# Mezz_Board.net
KiCad netlist of a schematic drawn in Altium Designer
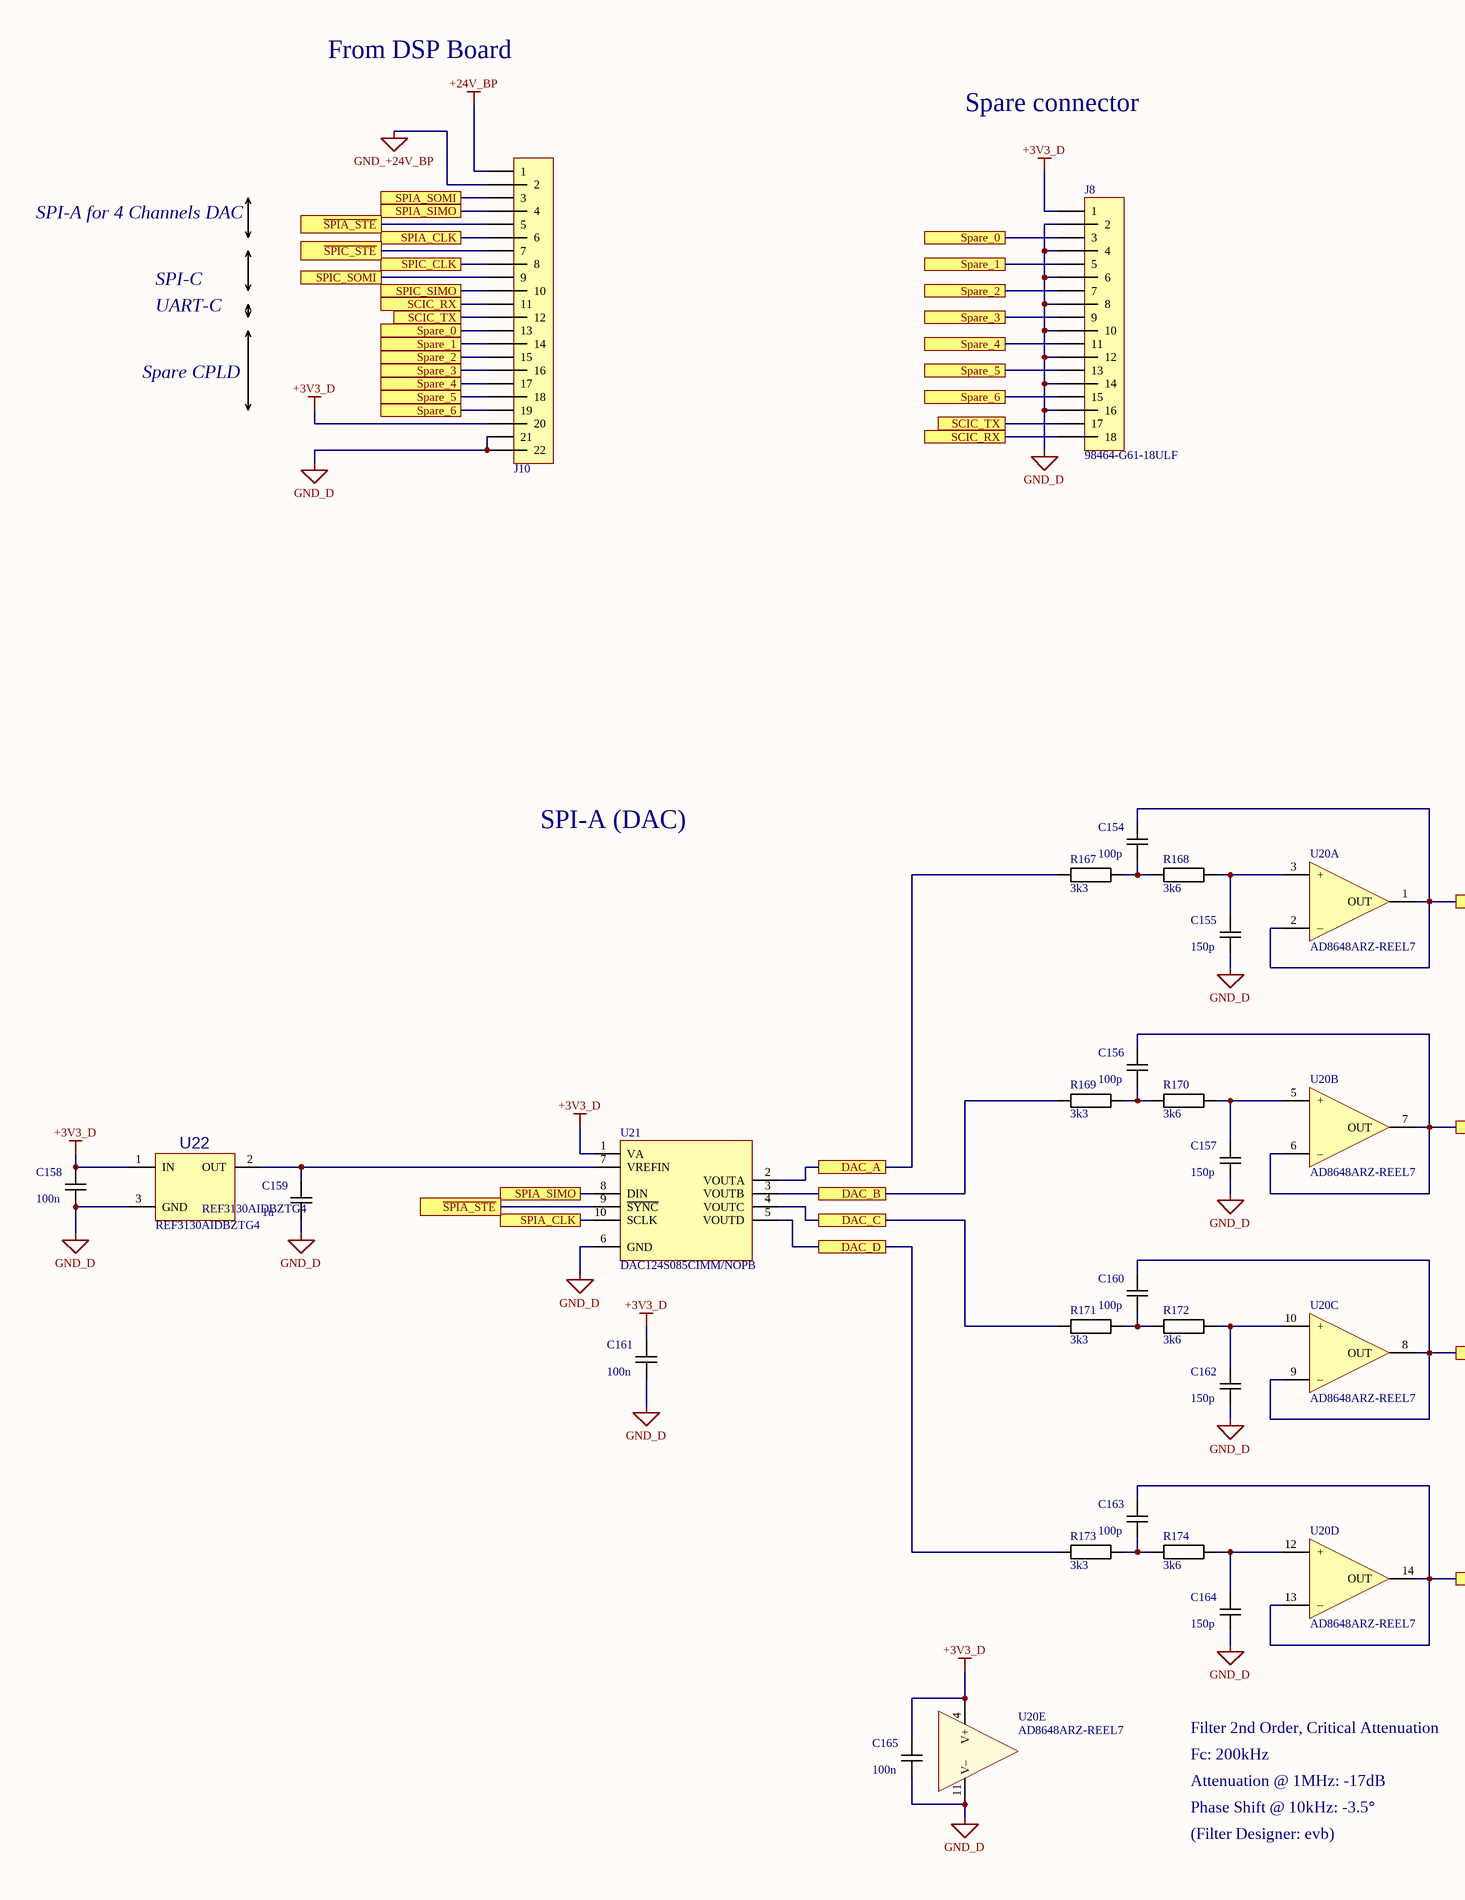
[diagram p0: Mezz_Board.SchDoc, left]
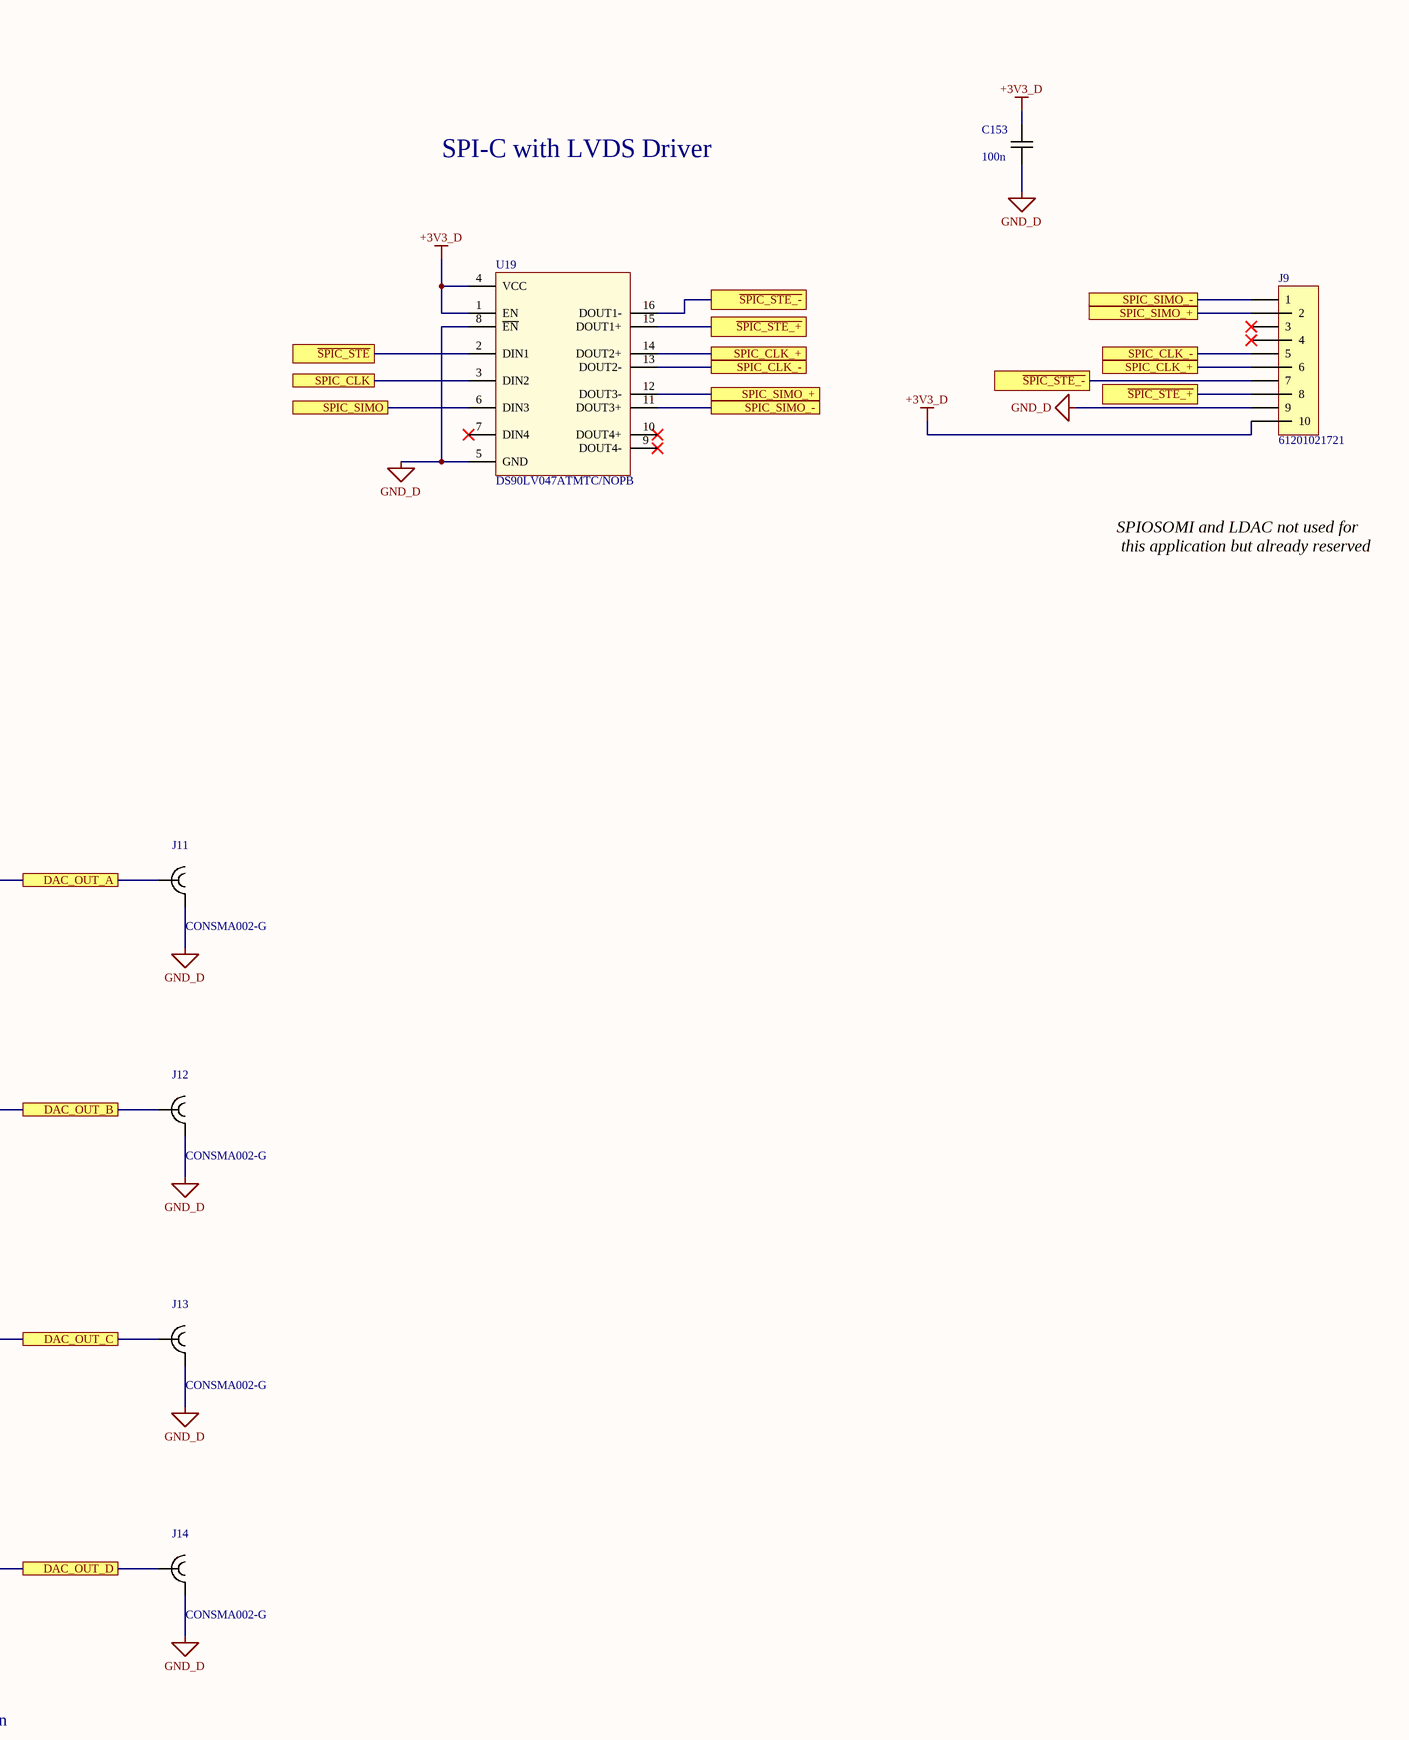
[diagram p1: Mezz_Board.SchDoc, right]

(export (version "E")
  (design (tool "Eeschema 10.0.6"))
  (components
    (comp (ref "C153")
      (value "100n")
      (footprint "CAPACITOR 2012 REFLOW")
      (description "Capacitor X7R 10% 50V 2012(0805)")
      (libsource (lib "Capacitor") (part "Capacitor"))
    )
    (comp (ref "C154")
      (value "100p")
      (footprint "CAPACITOR 2012 REFLOW")
      (description "Capacitor X7R 10% 50V 2012(0805)")
      (libsource (lib "Capacitor") (part "Capacitor"))
    )
    (comp (ref "C155")
      (value "150p")
      (footprint "CAPACITOR 2012 REFLOW")
      (description "Capacitor X7R 10% 50V 2012(0805)")
      (libsource (lib "Capacitor") (part "Capacitor"))
    )
    (comp (ref "C156")
      (value "100p")
      (footprint "CAPACITOR 2012 REFLOW")
      (description "Capacitor X7R 10% 50V 2012(0805)")
      (libsource (lib "Capacitor") (part "Capacitor"))
    )
    (comp (ref "C157")
      (value "150p")
      (footprint "CAPACITOR 2012 REFLOW")
      (description "Capacitor X7R 10% 50V 2012(0805)")
      (libsource (lib "Capacitor") (part "Capacitor"))
    )
    (comp (ref "C158")
      (value "100n")
      (footprint "CAPACITOR 2012 REFLOW")
      (description "Capacitor X7R 10% 50V 2012(0805)")
      (libsource (lib "Capacitor") (part "Capacitor"))
    )
    (comp (ref "C159")
      (value "1u")
      (footprint "CAPACITOR 2012 REFLOW")
      (description "Capacitor X7R 10% 10V 2012(0805)")
      (libsource (lib "Capacitor") (part "Capacitor"))
    )
    (comp (ref "C160")
      (value "100p")
      (footprint "CAPACITOR 2012 REFLOW")
      (description "Capacitor X7R 10% 50V 2012(0805)")
      (libsource (lib "Capacitor") (part "Capacitor"))
    )
    (comp (ref "C161")
      (value "100n")
      (footprint "CAPACITOR 1608 REFLOW")
      (description "Capacitor X7R 10% 50V 1608(0603)")
      (libsource (lib "Capacitor") (part "Capacitor"))
    )
    (comp (ref "C162")
      (value "150p")
      (footprint "CAPACITOR 2012 REFLOW")
      (description "Capacitor X7R 10% 50V 2012(0805)")
      (libsource (lib "Capacitor") (part "Capacitor"))
    )
    (comp (ref "C163")
      (value "100p")
      (footprint "CAPACITOR 2012 REFLOW")
      (description "Capacitor X7R 10% 50V 2012(0805)")
      (libsource (lib "Capacitor") (part "Capacitor"))
    )
    (comp (ref "C164")
      (value "150p")
      (footprint "CAPACITOR 2012 REFLOW")
      (description "Capacitor X7R 10% 50V 2012(0805)")
      (libsource (lib "Capacitor") (part "Capacitor"))
    )
    (comp (ref "C165")
      (value "100n")
      (footprint "CAPACITOR 1608 REFLOW")
      (description "Capacitor X7R 10% 50V 1608(0603)")
      (libsource (lib "Capacitor") (part "Capacitor"))
    )
    (comp (ref "J8")
      (value "98464-G61-18ULF")
      (footprint "FlatCable2x9 2MM Right Angle TH FCI 98614-G61-18ULF")
      (description "FlatCable2x9")
      (fields (field (name "MANUFACTURER") "Amphenol FCI"))
      (libsource (lib "Connector") (part "FlatCable2x9"))
    )
    (comp (ref "J9")
      (value "61201021721")
      (footprint "FlatCable2x5 2.54MM RIGHT ANGLE TH")
      (description "FlatCable2x5")
      (fields (field (name "MANUFACTURER") "Wurth Elektronik"))
      (libsource (lib "Connector") (part "FlatCable2x5"))
    )
    (comp (ref "J10")
      (value "*")
      (footprint "PinHeader2x11 P2.54 A")
      (description "Plug connector")
      (libsource (lib "PinHeader") (part "PinHeader2x11"))
    )
    (comp (ref "J11")
      (value "CONSMA002-G")
      (footprint "SMA TH Right Angle Linx CONSMA002")
      (description "SMA TH RIGHT ANGLE LINX CONSMA002")
      (fields (field (name "MANUFACTURER") "Linx Technologies"))
      (libsource (lib "Connector") (part "SMA TH RIGHT ANGLE LINX CONSMA002"))
    )
    (comp (ref "J12")
      (value "CONSMA002-G")
      (footprint "SMA TH Right Angle Linx CONSMA002")
      (description "SMA TH RIGHT ANGLE LINX CONSMA002")
      (fields (field (name "MANUFACTURER") "Linx Technologies"))
      (libsource (lib "Connector") (part "SMA TH RIGHT ANGLE LINX CONSMA002"))
    )
    (comp (ref "J13")
      (value "CONSMA002-G")
      (footprint "SMA TH Right Angle Linx CONSMA002")
      (description "SMA TH RIGHT ANGLE LINX CONSMA002")
      (fields (field (name "MANUFACTURER") "Linx Technologies"))
      (libsource (lib "Connector") (part "SMA TH RIGHT ANGLE LINX CONSMA002"))
    )
    (comp (ref "J14")
      (value "CONSMA002-G")
      (footprint "SMA TH Right Angle Linx CONSMA002")
      (description "SMA TH RIGHT ANGLE LINX CONSMA002")
      (fields (field (name "MANUFACTURER") "Linx Technologies"))
      (libsource (lib "Connector") (part "SMA TH RIGHT ANGLE LINX CONSMA002"))
    )
    (comp (ref "R167")
      (value "3k3")
      (footprint "RESISTOR 2012 REFLOW")
      (description "Resistor 1% 50V 125mW 2012(0805)")
      (libsource (lib "Resistor") (part "Resistor"))
    )
    (comp (ref "R168")
      (value "3k6")
      (footprint "RESISTOR 2012 REFLOW")
      (description "Resistor 1% 50V 125mW 2012(0805)")
      (libsource (lib "Resistor") (part "Resistor"))
    )
    (comp (ref "R169")
      (value "3k3")
      (footprint "RESISTOR 2012 REFLOW")
      (description "Resistor 1% 50V 125mW 2012(0805)")
      (libsource (lib "Resistor") (part "Resistor"))
    )
    (comp (ref "R170")
      (value "3k6")
      (footprint "RESISTOR 2012 REFLOW")
      (description "Resistor 1% 50V 125mW 2012(0805)")
      (libsource (lib "Resistor") (part "Resistor"))
    )
    (comp (ref "R171")
      (value "3k3")
      (footprint "RESISTOR 2012 REFLOW")
      (description "Resistor 1% 50V 125mW 2012(0805)")
      (libsource (lib "Resistor") (part "Resistor"))
    )
    (comp (ref "R172")
      (value "3k6")
      (footprint "RESISTOR 2012 REFLOW")
      (description "Resistor 1% 50V 125mW 2012(0805)")
      (libsource (lib "Resistor") (part "Resistor"))
    )
    (comp (ref "R173")
      (value "3k3")
      (footprint "RESISTOR 2012 REFLOW")
      (description "Resistor 1% 50V 125mW 2012(0805)")
      (libsource (lib "Resistor") (part "Resistor"))
    )
    (comp (ref "R174")
      (value "3k6")
      (footprint "RESISTOR 2012 REFLOW")
      (description "Resistor 1% 50V 125mW 2012(0805)")
      (libsource (lib "Resistor") (part "Resistor"))
    )
    (comp (ref "U19")
      (value "DS90LV047ATMTC/NOPB")
      (footprint "TSSOP16 P0.65 C5.0x4.5 H1.1")
      (description "DS90LV047A 3-V LVDS Quad CMOS Differential Line Driver")
      (fields (field (name "MANUFACTURER") "Texas Instruments"))
      (libsource (lib "IntegratedCircuit") (part "DS90LV047A"))
    )
    (comp (ref "U20")
      (value "AD8648ARZ-REEL7")
      (footprint "SO14 P1.27 C4.0X8.8 H1.75")
      (description "Generic quad OPA 14 pins")
      (fields (field (name "MANUFACTURER") "Analog Devices"))
      (libsource (lib "Amplifier") (part "OPA QUAD"))
    )
    (comp (ref "U21")
      (value "DAC124S085CIMM/NOPB")
      (footprint "VSSOP10 P0.5 C3.1X3.1 H1.1")
      (description "DAC124S085 12-Bit Micro Power Quad Digital-to-Analog Converter With Rail-to-Rail Output")
      (fields (field (name "MANUFACTURER") "Texas Instruments"))
      (libsource (lib "Converter") (part "DAC124S085CIMM"))
    )
    (comp (ref "U22")
      (value "REF3130AIDBZTG4")
      (footprint "SOT23 P0.95 C1.6x3.0 H1.3")
      (description "Generic Positive Voltage Reference")
      (fields
        (field (name "ALTIUM_VALUE") "REF3130AIDBZTG4")
        (field (name "MANUFACTURER") "Texas Instruments")
      )
      (libsource (lib "Regulator") (part "REFERENCE SOT23 IN-OUT- GND"))
    )
  )
  (nets
    (net (code "1") (name "+3V3_D") (class "Default")
      (node (ref "C153") (pin "2") (pinfunction "2_2") (pintype "passive"))
      (node (ref "C158") (pin "2") (pinfunction "2_2") (pintype "passive"))
      (node (ref "C161") (pin "2") (pinfunction "2_2") (pintype "passive"))
      (node (ref "C165") (pin "2") (pinfunction "2_2") (pintype "passive"))
      (node (ref "J10") (pin "20") (pinfunction "20_20") (pintype "passive"))
      (node (ref "J8") (pin "1") (pinfunction "1_1") (pintype "passive"))
      (node (ref "J9") (pin "10") (pinfunction "10_10") (pintype "passive"))
      (node (ref "U19") (pin "1") (pinfunction "EN_1") (pintype "passive"))
      (node (ref "U19") (pin "4") (pinfunction "VCC_4") (pintype "passive"))
      (node (ref "U20") (pin "4") (pinfunction "V+_4") (pintype "passive"))
      (node (ref "U21") (pin "1") (pinfunction "VA_1") (pintype "passive"))
      (node (ref "U22") (pin "1") (pinfunction "IN_1") (pintype "passive"))
    )
    (net (code "2") (name "+24V_BP") (class "Default")
      (node (ref "J10") (pin "1") (pinfunction "1_1") (pintype "passive"))
    )
    (net (code "3") (name "/DAC_A") (class "Default")
      (node (ref "R167") (pin "1") (pinfunction "1_1") (pintype "passive"))
      (node (ref "U21") (pin "2") (pinfunction "VOUTA_2") (pintype "passive"))
    )
    (net (code "4") (name "/DAC_B") (class "Default")
      (node (ref "R169") (pin "1") (pinfunction "1_1") (pintype "passive"))
      (node (ref "U21") (pin "3") (pinfunction "VOUTB_3") (pintype "passive"))
    )
    (net (code "5") (name "/DAC_C") (class "Default")
      (node (ref "R171") (pin "1") (pinfunction "1_1") (pintype "passive"))
      (node (ref "U21") (pin "4") (pinfunction "VOUTC_4") (pintype "passive"))
    )
    (net (code "6") (name "/DAC_D") (class "Default")
      (node (ref "R173") (pin "1") (pinfunction "1_1") (pintype "passive"))
      (node (ref "U21") (pin "5") (pinfunction "VOUTD_5") (pintype "passive"))
    )
    (net (code "7") (name "/DAC_OUT_A") (class "Default")
      (node (ref "C154") (pin "2") (pinfunction "2_2") (pintype "passive"))
      (node (ref "J11") (pin "1") (pinfunction "1_1") (pintype "passive"))
      (node (ref "U20") (pin "1") (pinfunction "OUT_1") (pintype "passive"))
      (node (ref "U20") (pin "2") (pinfunction "–_2") (pintype "passive"))
    )
    (net (code "8") (name "/DAC_OUT_B") (class "Default")
      (node (ref "C156") (pin "2") (pinfunction "2_2") (pintype "passive"))
      (node (ref "J12") (pin "1") (pinfunction "1_1") (pintype "passive"))
      (node (ref "U20") (pin "6") (pinfunction "–_6") (pintype "passive"))
      (node (ref "U20") (pin "7") (pinfunction "OUT_7") (pintype "passive"))
    )
    (net (code "9") (name "/DAC_OUT_C") (class "Default")
      (node (ref "C160") (pin "2") (pinfunction "2_2") (pintype "passive"))
      (node (ref "J13") (pin "1") (pinfunction "1_1") (pintype "passive"))
      (node (ref "U20") (pin "8") (pinfunction "OUT_8") (pintype "passive"))
      (node (ref "U20") (pin "9") (pinfunction "–_9") (pintype "passive"))
    )
    (net (code "10") (name "/DAC_OUT_D") (class "Default")
      (node (ref "C163") (pin "2") (pinfunction "2_2") (pintype "passive"))
      (node (ref "J14") (pin "1") (pinfunction "1_1") (pintype "passive"))
      (node (ref "U20") (pin "13") (pinfunction "–_13") (pintype "passive"))
      (node (ref "U20") (pin "14") (pinfunction "OUT_14") (pintype "passive"))
    )
    (net (code "11") (name "/SCIC_RX") (class "Default")
      (node (ref "J10") (pin "11") (pinfunction "11_11") (pintype "passive"))
      (node (ref "J8") (pin "18") (pinfunction "18_18") (pintype "passive"))
    )
    (net (code "12") (name "/SCIC_TX") (class "Default")
      (node (ref "J10") (pin "12") (pinfunction "12_12") (pintype "passive"))
      (node (ref "J8") (pin "17") (pinfunction "17_17") (pintype "passive"))
    )
    (net (code "13") (name "/SPIA_CLK") (class "Default")
      (node (ref "J10") (pin "6") (pinfunction "6_6") (pintype "passive"))
      (node (ref "U21") (pin "10") (pinfunction "SCLK_10") (pintype "passive"))
    )
    (net (code "14") (name "/SPIA_SIMO") (class "Default")
      (node (ref "J10") (pin "4") (pinfunction "4_4") (pintype "passive"))
      (node (ref "U21") (pin "8") (pinfunction "DIN_8") (pintype "passive"))
    )
    (net (code "15") (name "/SPIA_SOMI") (class "Default")
      (node (ref "J10") (pin "3") (pinfunction "3_3") (pintype "passive"))
    )
    (net (code "16") (name "/SPIC_CLK") (class "Default")
      (node (ref "J10") (pin "8") (pinfunction "8_8") (pintype "passive"))
      (node (ref "U19") (pin "3") (pinfunction "DIN2_3") (pintype "passive"))
    )
    (net (code "17") (name "/SPIC_CLK_+") (class "Default")
      (node (ref "J9") (pin "6") (pinfunction "6_6") (pintype "passive"))
      (node (ref "U19") (pin "14") (pinfunction "DOUT2+_14") (pintype "passive"))
    )
    (net (code "18") (name "/SPIC_CLK_-") (class "Default")
      (node (ref "J9") (pin "5") (pinfunction "5_5") (pintype "passive"))
      (node (ref "U19") (pin "13") (pinfunction "DOUT2-_13") (pintype "passive"))
    )
    (net (code "19") (name "/SPIC_SIMO") (class "Default")
      (node (ref "J10") (pin "10") (pinfunction "10_10") (pintype "passive"))
      (node (ref "U19") (pin "6") (pinfunction "DIN3_6") (pintype "passive"))
    )
    (net (code "20") (name "/SPIC_SIMO_+") (class "Default")
      (node (ref "J9") (pin "2") (pinfunction "2_2") (pintype "passive"))
      (node (ref "U19") (pin "12") (pinfunction "DOUT3-_12") (pintype "passive"))
    )
    (net (code "21") (name "/SPIC_SIMO_-") (class "Default")
      (node (ref "J9") (pin "1") (pinfunction "1_1") (pintype "passive"))
      (node (ref "U19") (pin "11") (pinfunction "DOUT3+_11") (pintype "passive"))
    )
    (net (code "22") (name "/SPIC_SOMI") (class "Default")
      (node (ref "J10") (pin "9") (pinfunction "9_9") (pintype "passive"))
    )
    (net (code "23") (name "/Spare_0") (class "Default")
      (node (ref "J10") (pin "13") (pinfunction "13_13") (pintype "passive"))
      (node (ref "J8") (pin "3") (pinfunction "3_3") (pintype "passive"))
    )
    (net (code "24") (name "/Spare_1") (class "Default")
      (node (ref "J10") (pin "14") (pinfunction "14_14") (pintype "passive"))
      (node (ref "J8") (pin "5") (pinfunction "5_5") (pintype "passive"))
    )
    (net (code "25") (name "/Spare_2") (class "Default")
      (node (ref "J10") (pin "15") (pinfunction "15_15") (pintype "passive"))
      (node (ref "J8") (pin "7") (pinfunction "7_7") (pintype "passive"))
    )
    (net (code "26") (name "/Spare_3") (class "Default")
      (node (ref "J10") (pin "16") (pinfunction "16_16") (pintype "passive"))
      (node (ref "J8") (pin "9") (pinfunction "9_9") (pintype "passive"))
    )
    (net (code "27") (name "/Spare_4") (class "Default")
      (node (ref "J10") (pin "17") (pinfunction "17_17") (pintype "passive"))
      (node (ref "J8") (pin "11") (pinfunction "11_11") (pintype "passive"))
    )
    (net (code "28") (name "/Spare_5") (class "Default")
      (node (ref "J10") (pin "18") (pinfunction "18_18") (pintype "passive"))
      (node (ref "J8") (pin "13") (pinfunction "13_13") (pintype "passive"))
    )
    (net (code "29") (name "/Spare_6") (class "Default")
      (node (ref "J10") (pin "19") (pinfunction "19_19") (pintype "passive"))
      (node (ref "J8") (pin "15") (pinfunction "15_15") (pintype "passive"))
    )
    (net (code "30") (name "/~{SPIA_STE}") (class "Default")
      (node (ref "J10") (pin "5") (pinfunction "5_5") (pintype "passive"))
      (node (ref "U21") (pin "9") (pinfunction "~{SYNC}_9") (pintype "passive"))
    )
    (net (code "31") (name "/~{SPIC_STE_+}") (class "Default")
      (node (ref "J9") (pin "8") (pinfunction "8_8") (pintype "passive"))
      (node (ref "U19") (pin "15") (pinfunction "DOUT1+_15") (pintype "passive"))
    )
    (net (code "32") (name "/~{SPIC_STE_-}") (class "Default")
      (node (ref "J9") (pin "7") (pinfunction "7_7") (pintype "passive"))
      (node (ref "U19") (pin "16") (pinfunction "DOUT1-_16") (pintype "passive"))
    )
    (net (code "33") (name "/~{SPIC_STE}") (class "Default")
      (node (ref "J10") (pin "7") (pinfunction "7_7") (pintype "passive"))
      (node (ref "U19") (pin "2") (pinfunction "DIN1_2") (pintype "passive"))
    )
    (net (code "34") (name "GND_+24V_BP") (class "Default")
      (node (ref "J10") (pin "2") (pinfunction "2_2") (pintype "passive"))
    )
    (net (code "35") (name "GND_D") (class "Default")
      (node (ref "C153") (pin "1") (pinfunction "1_1") (pintype "passive"))
      (node (ref "C155") (pin "1") (pinfunction "1_1") (pintype "passive"))
      (node (ref "C157") (pin "1") (pinfunction "1_1") (pintype "passive"))
      (node (ref "C158") (pin "1") (pinfunction "1_1") (pintype "passive"))
      (node (ref "C159") (pin "1") (pinfunction "1_1") (pintype "passive"))
      (node (ref "C161") (pin "1") (pinfunction "1_1") (pintype "passive"))
      (node (ref "C162") (pin "1") (pinfunction "1_1") (pintype "passive"))
      (node (ref "C164") (pin "1") (pinfunction "1_1") (pintype "passive"))
      (node (ref "C165") (pin "1") (pinfunction "1_1") (pintype "passive"))
      (node (ref "J10") (pin "21") (pinfunction "21_21") (pintype "passive"))
      (node (ref "J10") (pin "22") (pinfunction "22_22") (pintype "passive"))
      (node (ref "J11") (pin "2") (pinfunction "2_2") (pintype "passive"))
      (node (ref "J12") (pin "2") (pinfunction "2_2") (pintype "passive"))
      (node (ref "J13") (pin "2") (pinfunction "2_2") (pintype "passive"))
      (node (ref "J14") (pin "2") (pinfunction "2_2") (pintype "passive"))
      (node (ref "J8") (pin "10") (pinfunction "10_10") (pintype "passive"))
      (node (ref "J8") (pin "12") (pinfunction "12_12") (pintype "passive"))
      (node (ref "J8") (pin "14") (pinfunction "14_14") (pintype "passive"))
      (node (ref "J8") (pin "16") (pinfunction "16_16") (pintype "passive"))
      (node (ref "J8") (pin "2") (pinfunction "2_2") (pintype "passive"))
      (node (ref "J8") (pin "4") (pinfunction "4_4") (pintype "passive"))
      (node (ref "J8") (pin "6") (pinfunction "6_6") (pintype "passive"))
      (node (ref "J8") (pin "8") (pinfunction "8_8") (pintype "passive"))
      (node (ref "J9") (pin "9") (pinfunction "9_9") (pintype "passive"))
      (node (ref "U19") (pin "5") (pinfunction "GND_5") (pintype "passive"))
      (node (ref "U19") (pin "8") (pinfunction "~{EN}_8") (pintype "passive"))
      (node (ref "U20") (pin "11") (pinfunction "V–_11") (pintype "passive"))
      (node (ref "U21") (pin "6") (pinfunction "GND_6") (pintype "passive"))
      (node (ref "U22") (pin "3") (pinfunction "GND_3") (pintype "passive"))
    )
    (net (code "36") (name "Net-(C154-Pad1)") (class "Default")
      (node (ref "C154") (pin "1") (pinfunction "1_1") (pintype "passive"))
      (node (ref "R167") (pin "2") (pinfunction "2_2") (pintype "passive"))
      (node (ref "R168") (pin "1") (pinfunction "1_1") (pintype "passive"))
    )
    (net (code "37") (name "Net-(C156-Pad1)") (class "Default")
      (node (ref "C156") (pin "1") (pinfunction "1_1") (pintype "passive"))
      (node (ref "R169") (pin "2") (pinfunction "2_2") (pintype "passive"))
      (node (ref "R170") (pin "1") (pinfunction "1_1") (pintype "passive"))
    )
    (net (code "38") (name "Net-(C160-Pad1)") (class "Default")
      (node (ref "C160") (pin "1") (pinfunction "1_1") (pintype "passive"))
      (node (ref "R171") (pin "2") (pinfunction "2_2") (pintype "passive"))
      (node (ref "R172") (pin "1") (pinfunction "1_1") (pintype "passive"))
    )
    (net (code "39") (name "Net-(C163-Pad1)") (class "Default")
      (node (ref "C163") (pin "1") (pinfunction "1_1") (pintype "passive"))
      (node (ref "R173") (pin "2") (pinfunction "2_2") (pintype "passive"))
      (node (ref "R174") (pin "1") (pinfunction "1_1") (pintype "passive"))
    )
    (net (code "40") (name "Net-(U20A-+)") (class "Default")
      (node (ref "C155") (pin "2") (pinfunction "2_2") (pintype "passive"))
      (node (ref "R168") (pin "2") (pinfunction "2_2") (pintype "passive"))
      (node (ref "U20") (pin "3") (pinfunction "+_3") (pintype "passive"))
    )
    (net (code "41") (name "Net-(U20B-+)") (class "Default")
      (node (ref "C157") (pin "2") (pinfunction "2_2") (pintype "passive"))
      (node (ref "R170") (pin "2") (pinfunction "2_2") (pintype "passive"))
      (node (ref "U20") (pin "5") (pinfunction "+_5") (pintype "passive"))
    )
    (net (code "42") (name "Net-(U20C-+)") (class "Default")
      (node (ref "C162") (pin "2") (pinfunction "2_2") (pintype "passive"))
      (node (ref "R172") (pin "2") (pinfunction "2_2") (pintype "passive"))
      (node (ref "U20") (pin "10") (pinfunction "+_10") (pintype "passive"))
    )
    (net (code "43") (name "Net-(U20D-+)") (class "Default")
      (node (ref "C164") (pin "2") (pinfunction "2_2") (pintype "passive"))
      (node (ref "R174") (pin "2") (pinfunction "2_2") (pintype "passive"))
      (node (ref "U20") (pin "12") (pinfunction "+_12") (pintype "passive"))
    )
    (net (code "44") (name "Net-(U21-VREFIN)") (class "Default")
      (node (ref "C159") (pin "2") (pinfunction "2_2") (pintype "passive"))
      (node (ref "U21") (pin "7") (pinfunction "VREFIN_7") (pintype "passive"))
      (node (ref "U22") (pin "2") (pinfunction "OUT_2") (pintype "passive"))
    )
    (net (code "45") (name "unconnected-(J9-Pad3)") (class "Default")
      (node (ref "J9") (pin "3") (pinfunction "3_3") (pintype "passive+no_connect"))
    )
    (net (code "46") (name "unconnected-(J9-Pad4)") (class "Default")
      (node (ref "J9") (pin "4") (pinfunction "4_4") (pintype "passive+no_connect"))
    )
    (net (code "47") (name "unconnected-(U19-DIN4-Pad7)") (class "Default")
      (node (ref "U19") (pin "7") (pinfunction "DIN4_7") (pintype "passive+no_connect"))
    )
    (net (code "48") (name "unconnected-(U19-DOUT4+-Pad10)") (class "Default")
      (node (ref "U19") (pin "10") (pinfunction "DOUT4+_10") (pintype "passive+no_connect"))
    )
    (net (code "49") (name "unconnected-(U19-DOUT4--Pad9)") (class "Default")
      (node (ref "U19") (pin "9") (pinfunction "DOUT4-_9") (pintype "passive+no_connect"))
    )
  )
)
